# SensWear_DaughterBoard.net
KiCad netlist of a schematic drawn in Altium Designer
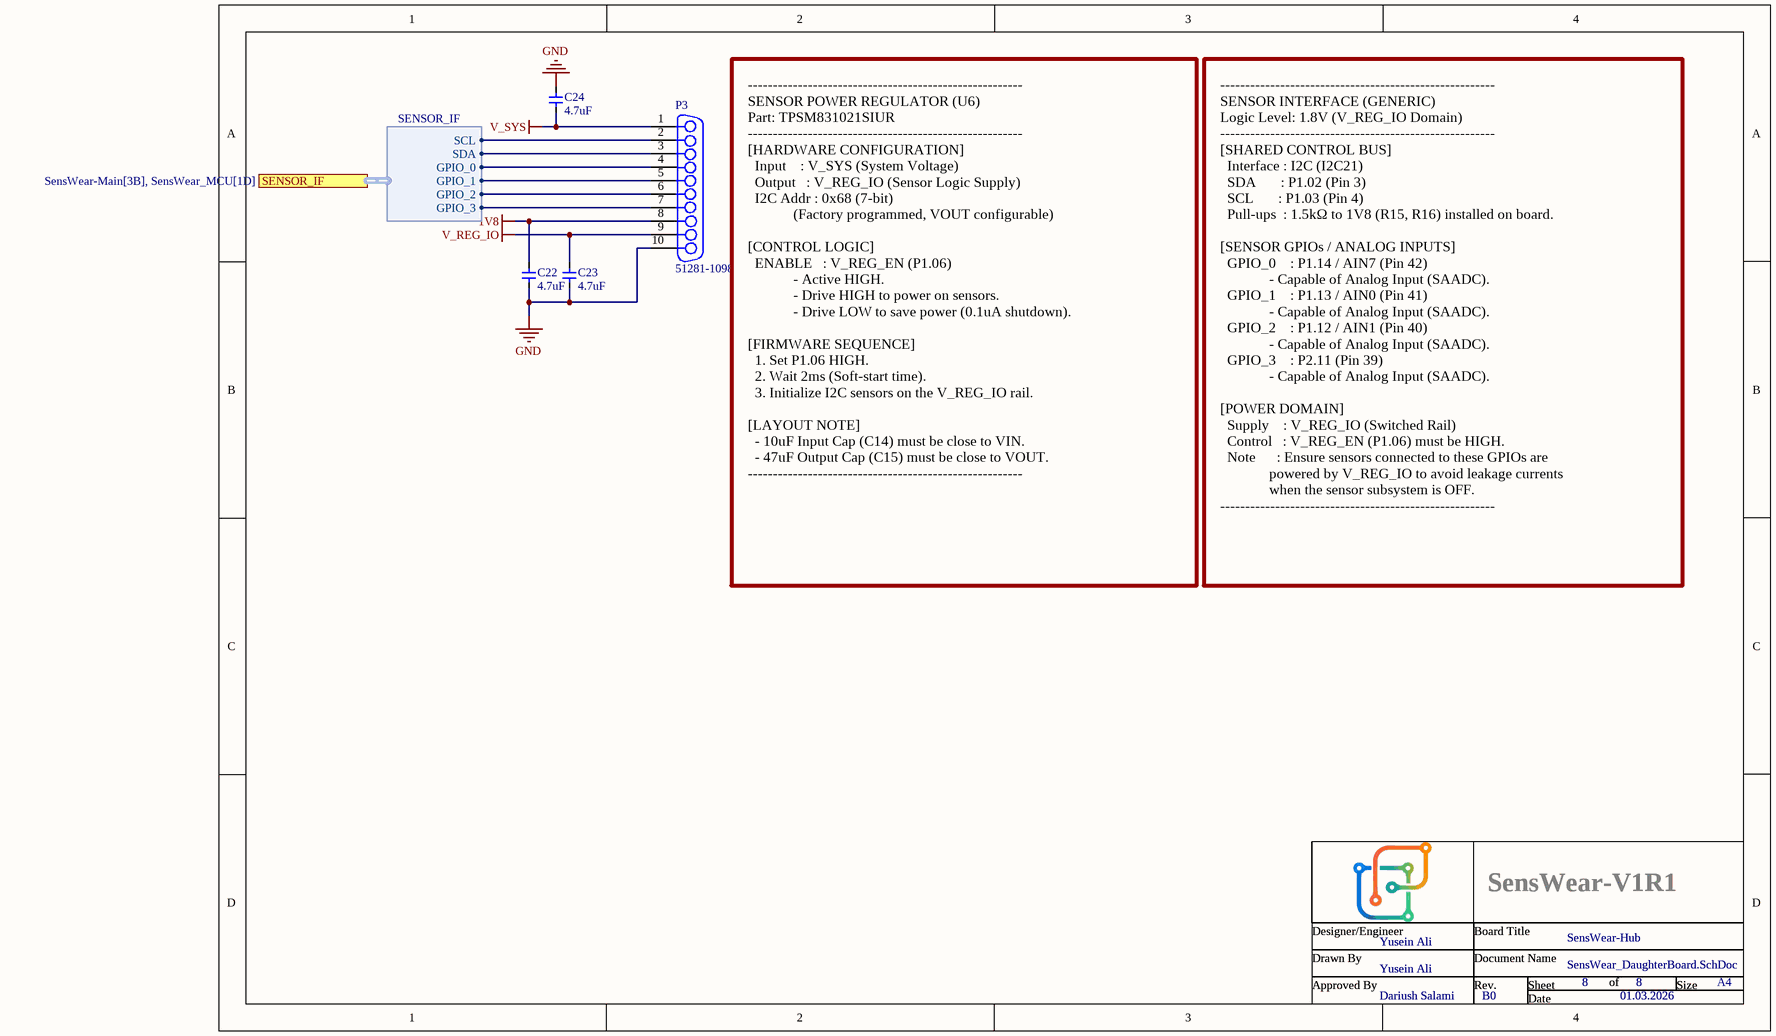
[diagram p0: SensWear_DaughterBoard.SchDoc]

(export (version "E")
  (design (tool "Eeschema 10.0.6"))
  (components
    (comp (ref "C22")
      (value "4.7uF")
      (footprint "CAPC1005X05N")
      (description "Multilayer Ceramic Capacitor, 4.7 uF, 10 V, ± 20%, X5R, 0402 [1005 Metric]")
      (fields
        (field (name "MANUFACTURER") "Murata")
        (field (name "MANUFACTURER PART NUMBER") "GRM155R61A475MEAAD")
      )
      (libsource (lib "SensWearComponents") (part "GRM155R61A475MEAAD__2"))
    )
    (comp (ref "C23")
      (value "4.7uF")
      (footprint "CAPC1005X05N")
      (description "Multilayer Ceramic Capacitor, 4.7 uF, 10 V, ± 20%, X5R, 0402 [1005 Metric]")
      (fields
        (field (name "MANUFACTURER") "Murata")
        (field (name "MANUFACTURER PART NUMBER") "GRM155R61A475MEAAD")
      )
      (libsource (lib "SensWearComponents") (part "GRM155R61A475MEAAD__2"))
    )
    (comp (ref "C24")
      (value "4.7uF")
      (footprint "CAPC1005X05N")
      (description "Multilayer Ceramic Capacitor, 4.7 uF, 10 V, ± 20%, X5R, 0402 [1005 Metric]")
      (fields
        (field (name "MANUFACTURER") "Murata")
        (field (name "MANUFACTURER PART NUMBER") "GRM155R61A475MEAAD")
      )
      (libsource (lib "SensWearComponents") (part "GRM155R61A475MEAAD__2"))
    )
    (comp (ref "P3")
      (value "51281-1098")
      (footprint "51281-1098__3")
      (description "FFC/FPC Connector, Surface Mount, Right-Angle, Non-ZIF, Dual Contact Style")
      (fields (field (name "MANUFACTURER") "Molex"))
      (libsource (lib "SensWearComponents") (part "51281-1098"))
    )
  )
  (nets
    (net (code "2") (name "/GPIO_0") (class "Default")
      (node (ref "P3") (pin "4") (pinfunction "4_4") (pintype "passive"))
    )
    (net (code "3") (name "/GPIO_1") (class "Default")
      (node (ref "P3") (pin "5") (pinfunction "5_5") (pintype "passive"))
    )
    (net (code "4") (name "/GPIO_2") (class "Default")
      (node (ref "P3") (pin "6") (pinfunction "6_6") (pintype "passive"))
    )
    (net (code "5") (name "/GPIO_3") (class "Default")
      (node (ref "P3") (pin "7") (pinfunction "7_7") (pintype "passive"))
    )
    (net (code "6") (name "/SCL") (class "Default")
      (node (ref "P3") (pin "2") (pinfunction "2_2") (pintype "passive"))
    )
    (net (code "7") (name "/SDA") (class "Default")
      (node (ref "P3") (pin "3") (pinfunction "3_3") (pintype "passive"))
    )
    (net (code "9") (name "1V8") (class "Default")
      (node (ref "C22") (pin "2") (pinfunction "2_2") (pintype "passive"))
      (node (ref "P3") (pin "8") (pinfunction "8_8") (pintype "passive"))
    )
    (net (code "10") (name "GND") (class "Default")
      (node (ref "C22") (pin "1") (pinfunction "1_1") (pintype "passive"))
      (node (ref "C23") (pin "1") (pinfunction "1_1") (pintype "passive"))
      (node (ref "C24") (pin "2") (pinfunction "2_2") (pintype "passive"))
      (node (ref "P3") (pin "10") (pinfunction "10_10") (pintype "passive"))
    )
    (net (code "11") (name "V_REG_IO") (class "Default")
      (node (ref "C23") (pin "2") (pinfunction "2_2") (pintype "passive"))
      (node (ref "P3") (pin "9") (pinfunction "9_9") (pintype "passive"))
    )
    (net (code "12") (name "V_SYS") (class "Default")
      (node (ref "C24") (pin "1") (pinfunction "1_1") (pintype "passive"))
      (node (ref "P3") (pin "1") (pinfunction "1_1") (pintype "passive"))
    )
  )
)
